# DryerSignal.net
KiCad netlist of a schematic drawn in EAGLE
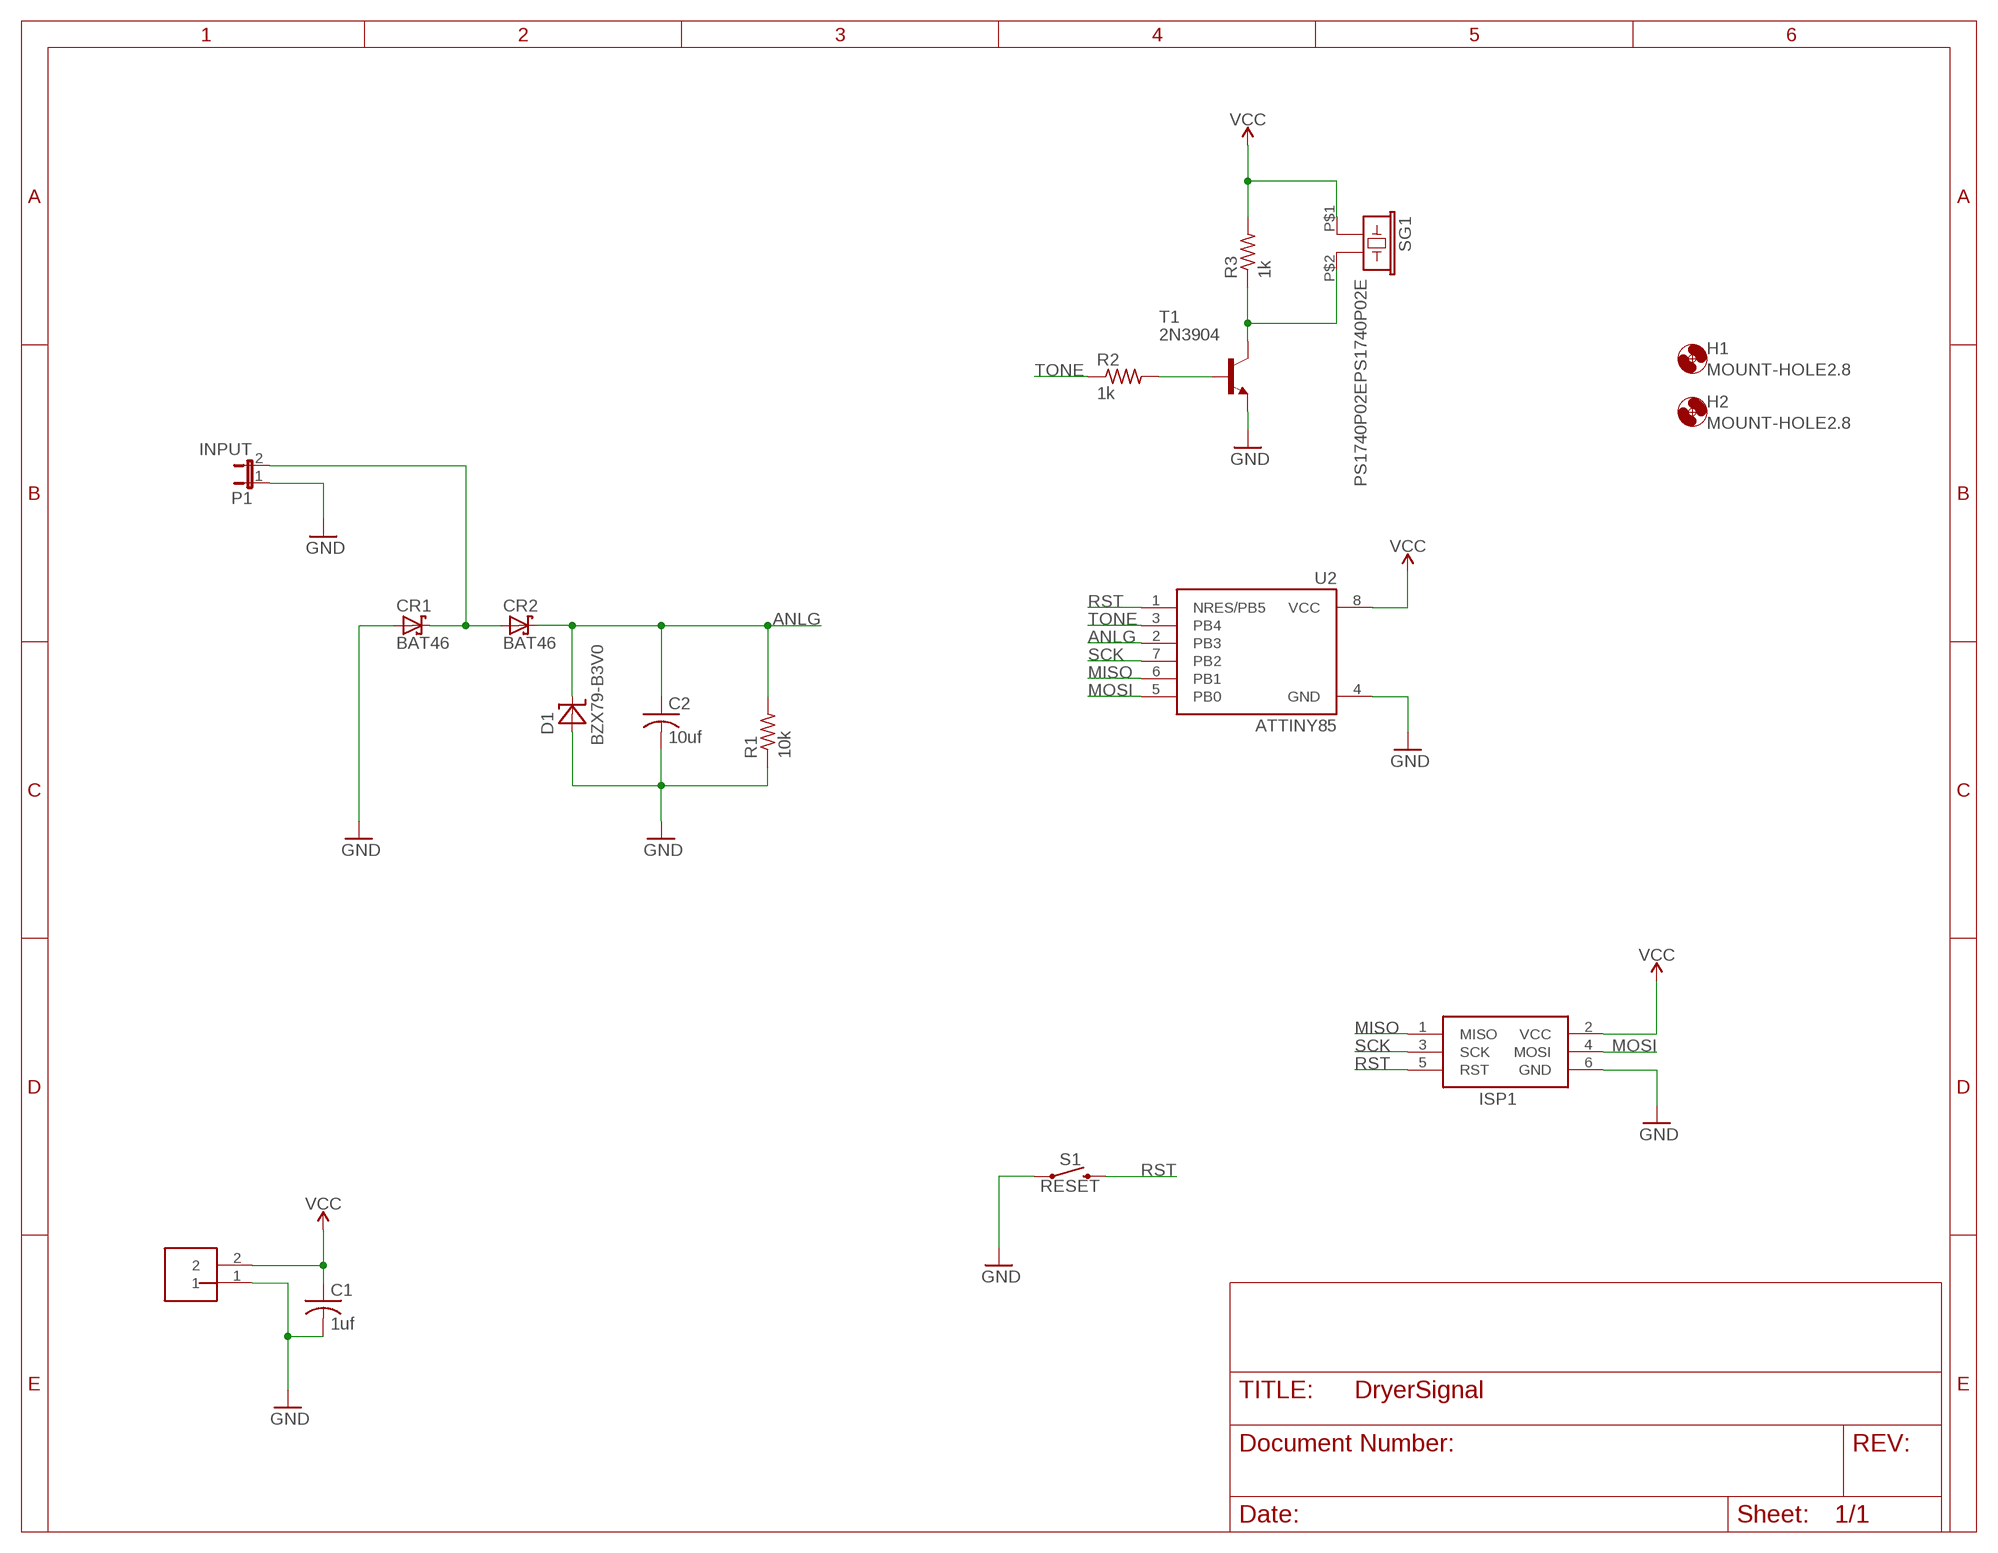
[diagram p0: schematic, sheet 1]

(export (version "E")
  (design (tool "Eeschema 10.0.6"))
  (components
    (comp (ref "C1")
      (value "1uf")
      (footprint "eagle-import:C050-025X075")
      (libsource (lib "eagle-import") (part "C-US050-025X075"))
    )
    (comp (ref "C2")
      (value "10uf")
      (footprint "eagle-import:C050-025X075")
      (libsource (lib "eagle-import") (part "C-US050-025X075"))
    )
    (comp (ref "CR1")
      (value "BAT46")
      (footprint "eagle-import:DO35-10")
      (libsource (lib "eagle-import") (part "BAT46"))
    )
    (comp (ref "CR2")
      (value "BAT46")
      (footprint "eagle-import:DO35-10")
      (libsource (lib "eagle-import") (part "BAT46"))
    )
    (comp (ref "D1")
      (value "BZX79-B3V0")
      (footprint "eagle-import:DO35-10")
      (libsource (lib "eagle-import") (part "BZX79"))
    )
    (comp (ref "H1")
      (value "MOUNT-HOLE2.8")
      (footprint "eagle-import:2,8")
      (libsource (lib "eagle-import") (part "MOUNT-HOLE2.8"))
    )
    (comp (ref "H2")
      (value "MOUNT-HOLE2.8")
      (footprint "eagle-import:2,8")
      (libsource (lib "eagle-import") (part "MOUNT-HOLE2.8"))
    )
    (comp (ref "ISP1")
      (value "AVRISP-BOX")
      (footprint "eagle-import:AVRISP-BOX")
      (libsource (lib "eagle-import") (part "AVRISP-BOX"))
    )
    (comp (ref "J1")
      (value "4.5v")
      (footprint "eagle-import:2_PIN_JST-XH")
      (libsource (lib "eagle-import") (part "2_PIN_JST-XH"))
    )
    (comp (ref "P1")
      (value "INPUT")
      (footprint "eagle-import:1X02")
      (libsource (lib "eagle-import") (part "PINHEADER-1X02PTH"))
    )
    (comp (ref "R1")
      (value "10k")
      (footprint "eagle-import:0207_10")
      (libsource (lib "eagle-import") (part "R-US_0207/10"))
    )
    (comp (ref "R2")
      (value "1k")
      (footprint "eagle-import:0207_10")
      (libsource (lib "eagle-import") (part "R-US_0207/10"))
    )
    (comp (ref "R3")
      (value "1k")
      (footprint "eagle-import:0207_10")
      (libsource (lib "eagle-import") (part "R-US_0207/10"))
    )
    (comp (ref "S1")
      (value "RESET")
      (footprint "eagle-import:1X02")
      (libsource (lib "eagle-import") (part "MOMENTARY-SWITCH-SPST-PANEL-MOUNT"))
    )
    (comp (ref "SG1")
      (value "PS1740P02EPS1740P02E")
      (footprint "eagle-import:PS1740P02E")
      (libsource (lib "eagle-import") (part "PS1740P02EPS1740P02E"))
    )
    (comp (ref "T1")
      (value "2N3904")
      (footprint "eagle-import:TO92")
      (libsource (lib "eagle-import") (part "2N3904"))
    )
    (comp (ref "U2")
      (value "ATTINY85")
      (footprint "eagle-import:PDIP08_300MIL")
      (libsource (lib "eagle-import") (part "ATTINY85PV-10"))
    )
  )
  (nets
    (net (code "1") (name "/ANLG") (class "Default")
      (node (ref "C2") (pin "1") (pinfunction "1_1") (pintype "passive"))
      (node (ref "CR2") (pin "C") (pinfunction "C_C") (pintype "passive"))
      (node (ref "D1") (pin "C") (pinfunction "C_C") (pintype "passive"))
      (node (ref "R1") (pin "2") (pinfunction "2_2") (pintype "passive"))
      (node (ref "U2") (pin "2") (pinfunction "PB3_2") (pintype "bidirectional"))
    )
    (net (code "2") (name "/MISO") (class "Default")
      (node (ref "ISP1") (pin "1") (pinfunction "MISO_1") (pintype "input"))
      (node (ref "U2") (pin "6") (pinfunction "PB1_6") (pintype "bidirectional"))
    )
    (net (code "3") (name "/MOSI") (class "Default")
      (node (ref "ISP1") (pin "4") (pinfunction "MOSI_4") (pintype "output"))
      (node (ref "U2") (pin "5") (pinfunction "PB0_5") (pintype "bidirectional"))
    )
    (net (code "4") (name "/RST") (class "Default")
      (node (ref "ISP1") (pin "5") (pinfunction "RST_5") (pintype "output"))
      (node (ref "S1") (pin "2") (pinfunction "2_2") (pintype "passive"))
      (node (ref "U2") (pin "1") (pinfunction "NRES/PB5_1") (pintype "bidirectional"))
    )
    (net (code "5") (name "/SCK") (class "Default")
      (node (ref "ISP1") (pin "3") (pinfunction "SCK_3") (pintype "output"))
      (node (ref "U2") (pin "7") (pinfunction "PB2_7") (pintype "bidirectional"))
    )
    (net (code "6") (name "/TONE") (class "Default")
      (node (ref "R2") (pin "1") (pinfunction "1_1") (pintype "passive"))
      (node (ref "U2") (pin "3") (pinfunction "PB4_3") (pintype "bidirectional"))
    )
    (net (code "7") (name "GND") (class "Default")
      (node (ref "C1") (pin "2") (pinfunction "2_2") (pintype "passive"))
      (node (ref "C2") (pin "2") (pinfunction "2_2") (pintype "passive"))
      (node (ref "CR1") (pin "A") (pinfunction "A_A") (pintype "passive"))
      (node (ref "D1") (pin "A") (pinfunction "A_A") (pintype "passive"))
      (node (ref "ISP1") (pin "6") (pinfunction "GND_6") (pintype "power_in"))
      (node (ref "J1") (pin "1") (pinfunction "1_1") (pintype "bidirectional"))
      (node (ref "P1") (pin "1") (pinfunction "1_1") (pintype "passive"))
      (node (ref "R1") (pin "1") (pinfunction "1_1") (pintype "passive"))
      (node (ref "S1") (pin "1") (pinfunction "1_1") (pintype "passive"))
      (node (ref "T1") (pin "3") (pinfunction "E_3") (pintype "passive"))
      (node (ref "U2") (pin "4") (pinfunction "GND_4") (pintype "power_in"))
    )
    (net (code "8") (name "Net-(CR1-PadC)") (class "Default")
      (node (ref "CR1") (pin "C") (pinfunction "C_C") (pintype "passive"))
      (node (ref "CR2") (pin "A") (pinfunction "A_A") (pintype "passive"))
      (node (ref "P1") (pin "2") (pinfunction "2_2") (pintype "passive"))
    )
    (net (code "9") (name "Net-(SG1-2)") (class "Default")
      (node (ref "R3") (pin "1") (pinfunction "1_1") (pintype "passive"))
      (node (ref "SG1") (pin "P$2") (pinfunction "2_P$2") (pintype "passive"))
      (node (ref "T1") (pin "1") (pinfunction "C_1") (pintype "passive"))
    )
    (net (code "10") (name "Net-(T1-B)") (class "Default")
      (node (ref "R2") (pin "2") (pinfunction "2_2") (pintype "passive"))
      (node (ref "T1") (pin "2") (pinfunction "B_2") (pintype "passive"))
    )
    (net (code "11") (name "VCC") (class "Default")
      (node (ref "C1") (pin "1") (pinfunction "1_1") (pintype "passive"))
      (node (ref "ISP1") (pin "2") (pinfunction "VCC_2") (pintype "power_in"))
      (node (ref "J1") (pin "2") (pinfunction "2_2") (pintype "bidirectional"))
      (node (ref "R3") (pin "2") (pinfunction "2_2") (pintype "passive"))
      (node (ref "SG1") (pin "P$1") (pinfunction "1_P$1") (pintype "passive"))
      (node (ref "U2") (pin "8") (pinfunction "VCC_8") (pintype "power_in"))
    )
  )
)
